# Animated_LED_Shifter_using_CD4017.net
KiCad netlist of a schematic drawn in EAGLE
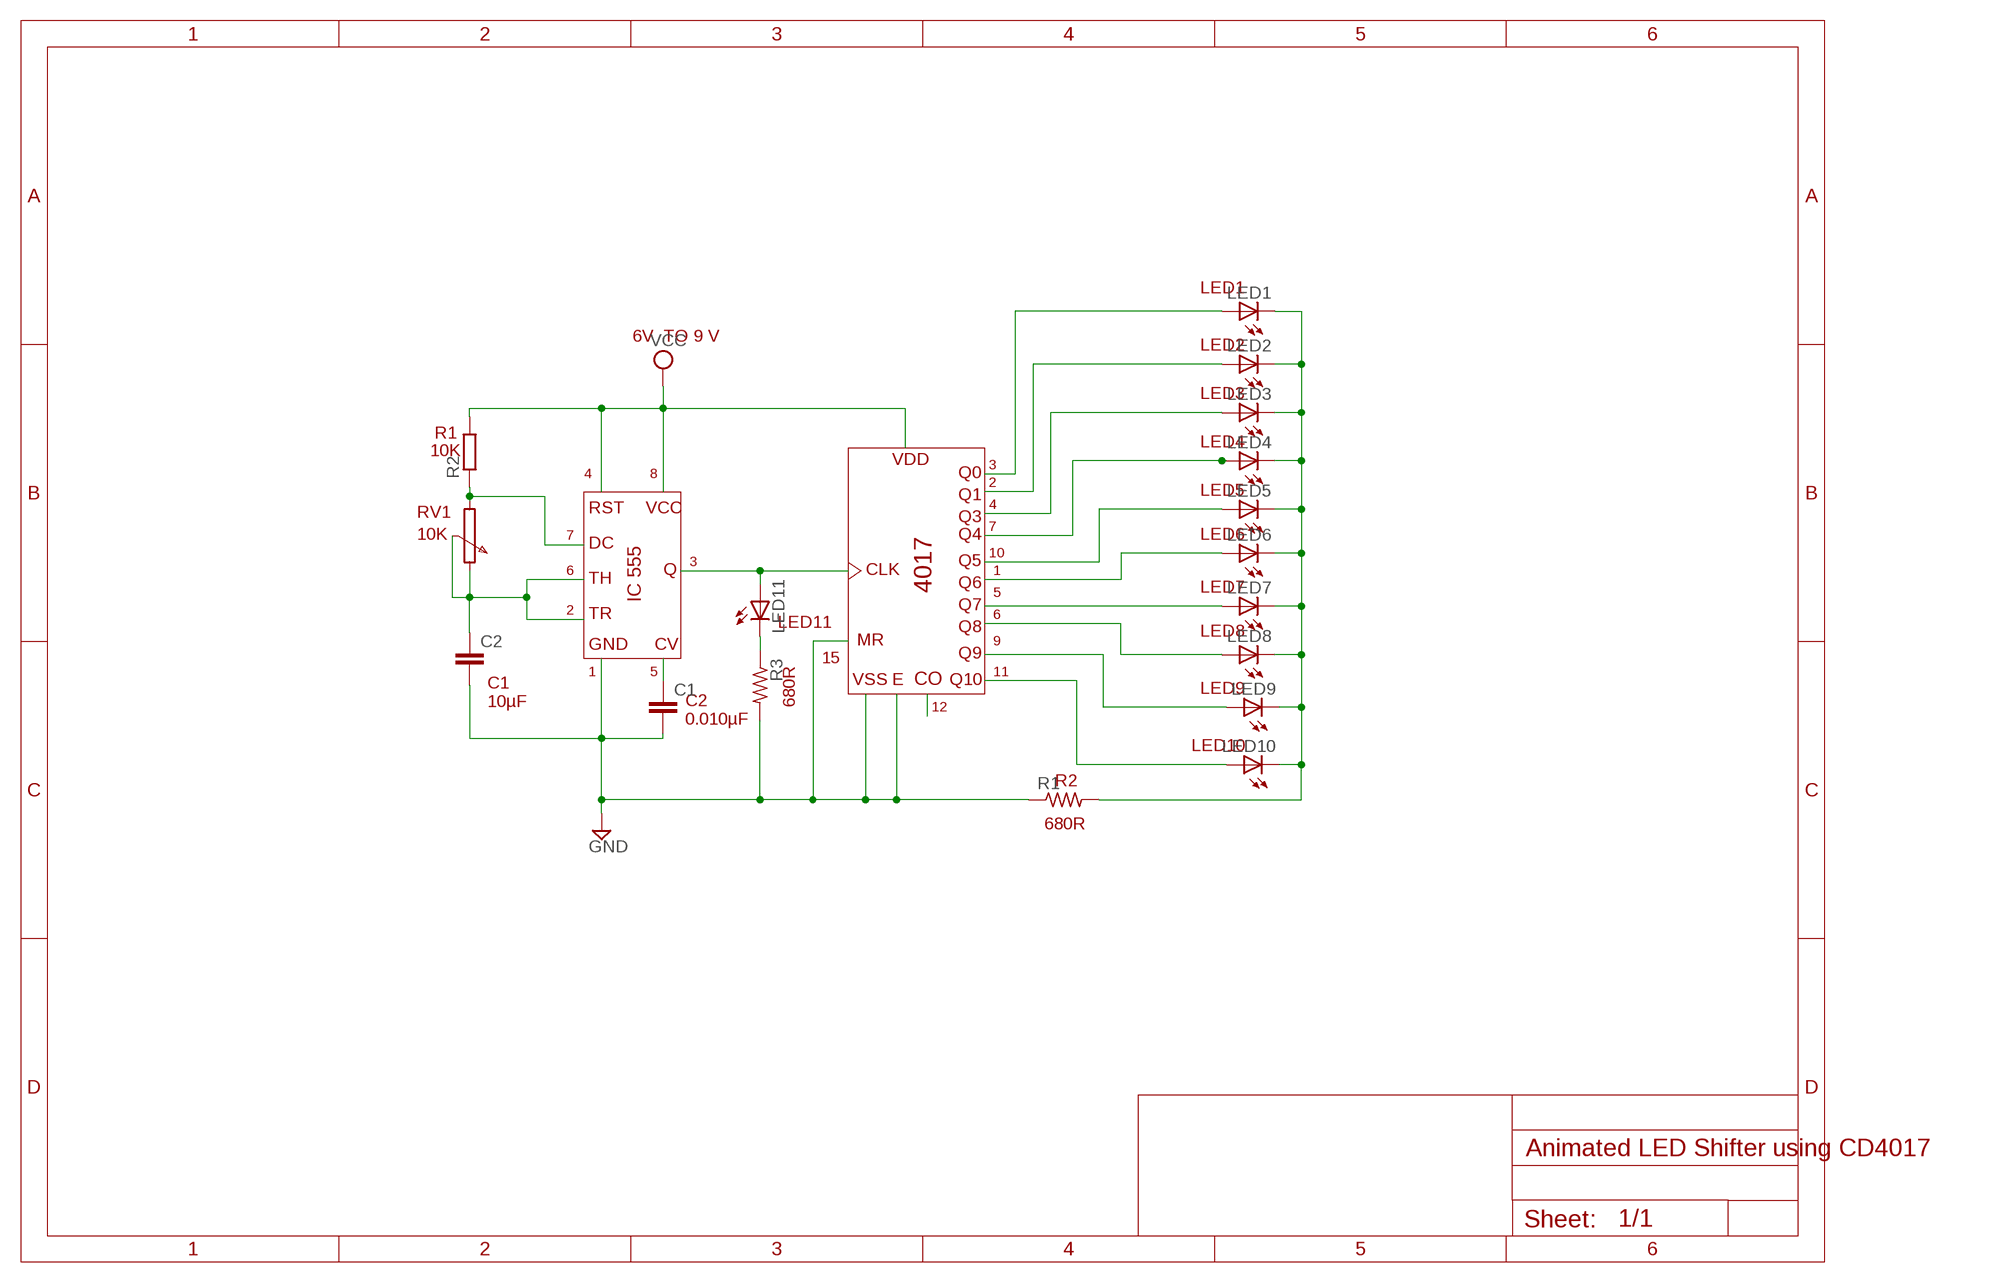
[diagram p0: schematic, sheet 1]

(export (version "E")
  (design (tool "Eeschema 10.0.6"))
  (components
    (comp (ref "C1")
      (value "C5/3.5")
      (footprint "eagle-import:C5B3.5")
      (libsource (lib "eagle-import") (part "C5/3.5"))
    )
    (comp (ref "C2")
      (value "C5/3.5")
      (footprint "eagle-import:C5B3.5")
      (libsource (lib "eagle-import") (part "C5/3.5"))
    )
    (comp (ref "LED1")
      (value "LEDMICRO-SIDELED")
      (footprint "eagle-import:MICRO-SIDELED")
      (libsource (lib "eagle-import") (part "LEDMICRO-SIDELED"))
    )
    (comp (ref "LED2")
      (value "LEDMICRO-SIDELED")
      (footprint "eagle-import:MICRO-SIDELED")
      (libsource (lib "eagle-import") (part "LEDMICRO-SIDELED"))
    )
    (comp (ref "LED3")
      (value "LEDMICRO-SIDELED")
      (footprint "eagle-import:MICRO-SIDELED")
      (libsource (lib "eagle-import") (part "LEDMICRO-SIDELED"))
    )
    (comp (ref "LED4")
      (value "LEDMICRO-SIDELED")
      (footprint "eagle-import:MICRO-SIDELED")
      (libsource (lib "eagle-import") (part "LEDMICRO-SIDELED"))
    )
    (comp (ref "LED5")
      (value "LEDMICRO-SIDELED")
      (footprint "eagle-import:MICRO-SIDELED")
      (libsource (lib "eagle-import") (part "LEDMICRO-SIDELED"))
    )
    (comp (ref "LED6")
      (value "LEDMICRO-SIDELED")
      (footprint "eagle-import:MICRO-SIDELED")
      (libsource (lib "eagle-import") (part "LEDMICRO-SIDELED"))
    )
    (comp (ref "LED7")
      (value "LEDMICRO-SIDELED")
      (footprint "eagle-import:MICRO-SIDELED")
      (libsource (lib "eagle-import") (part "LEDMICRO-SIDELED"))
    )
    (comp (ref "LED8")
      (value "LEDMICRO-SIDELED")
      (footprint "eagle-import:MICRO-SIDELED")
      (libsource (lib "eagle-import") (part "LEDMICRO-SIDELED"))
    )
    (comp (ref "LED9")
      (value "LEDMICRO-SIDELED")
      (footprint "eagle-import:MICRO-SIDELED")
      (libsource (lib "eagle-import") (part "LEDMICRO-SIDELED"))
    )
    (comp (ref "LED10")
      (value "LEDMICRO-SIDELED")
      (footprint "eagle-import:MICRO-SIDELED")
      (libsource (lib "eagle-import") (part "LEDMICRO-SIDELED"))
    )
    (comp (ref "LED11")
      (value "LEDMICRO-SIDELED")
      (footprint "eagle-import:MICRO-SIDELED")
      (libsource (lib "eagle-import") (part "LEDMICRO-SIDELED"))
    )
    (comp (ref "R1")
      (value "R-US_0207/10")
      (footprint "eagle-import:0207_10")
      (libsource (lib "eagle-import") (part "R-US_0207/10"))
    )
    (comp (ref "R2")
      (value "R-EU_0207/12")
      (footprint "eagle-import:0207_12")
      (libsource (lib "eagle-import") (part "R-EU_0207/12"))
    )
    (comp (ref "R3")
      (value "R-US_0207/10")
      (footprint "eagle-import:0207_10")
      (libsource (lib "eagle-import") (part "R-US_0207/10"))
    )
  )
  (nets
    (net (code "1") (name "GND") (class "Default")
      (node (ref "C1") (pin "2") (pinfunction "2_2") (pintype "passive"))
      (node (ref "C2") (pin "2") (pinfunction "2_2") (pintype "passive"))
      (node (ref "R1") (pin "1") (pinfunction "1_1") (pintype "passive"))
      (node (ref "R3") (pin "2") (pinfunction "2_2") (pintype "passive"))
    )
    (net (code "2") (name "Net-(LED1-PadC)") (class "Default")
      (node (ref "LED1") (pin "C") (pinfunction "C_C") (pintype "passive"))
      (node (ref "LED10") (pin "C") (pinfunction "C_C") (pintype "passive"))
      (node (ref "LED2") (pin "C") (pinfunction "C_C") (pintype "passive"))
      (node (ref "LED3") (pin "C") (pinfunction "C_C") (pintype "passive"))
      (node (ref "LED4") (pin "C") (pinfunction "C_C") (pintype "passive"))
      (node (ref "LED5") (pin "C") (pinfunction "C_C") (pintype "passive"))
      (node (ref "LED6") (pin "C") (pinfunction "C_C") (pintype "passive"))
      (node (ref "LED7") (pin "C") (pinfunction "C_C") (pintype "passive"))
      (node (ref "LED8") (pin "C") (pinfunction "C_C") (pintype "passive"))
      (node (ref "LED9") (pin "C") (pinfunction "C_C") (pintype "passive"))
      (node (ref "R1") (pin "2") (pinfunction "2_2") (pintype "passive"))
    )
    (net (code "3") (name "Net-(LED11-PadC)") (class "Default")
      (node (ref "LED11") (pin "C") (pinfunction "C_C") (pintype "passive"))
      (node (ref "R3") (pin "1") (pinfunction "1_1") (pintype "passive"))
    )
    (net (code "4") (name "VCC") (class "Default")
      (node (ref "R2") (pin "2") (pinfunction "2_2") (pintype "passive"))
    )
    (net (code "5") (name "unconnected-(C1-Pad1)") (class "Default")
      (node (ref "C1") (pin "1") (pinfunction "1_1") (pintype "passive"))
    )
    (net (code "6") (name "unconnected-(C2-Pad1)") (class "Default")
      (node (ref "C2") (pin "1") (pinfunction "1_1") (pintype "passive"))
    )
    (net (code "7") (name "unconnected-(LED1-PadA)") (class "Default")
      (node (ref "LED1") (pin "A") (pinfunction "A_A") (pintype "passive"))
    )
    (net (code "8") (name "unconnected-(LED2-PadA)") (class "Default")
      (node (ref "LED2") (pin "A") (pinfunction "A_A") (pintype "passive"))
    )
    (net (code "9") (name "unconnected-(LED3-PadA)") (class "Default")
      (node (ref "LED3") (pin "A") (pinfunction "A_A") (pintype "passive"))
    )
    (net (code "10") (name "unconnected-(LED4-PadA)") (class "Default")
      (node (ref "LED4") (pin "A") (pinfunction "A_A") (pintype "passive"))
    )
    (net (code "11") (name "unconnected-(LED5-PadA)") (class "Default")
      (node (ref "LED5") (pin "A") (pinfunction "A_A") (pintype "passive"))
    )
    (net (code "12") (name "unconnected-(LED6-PadA)") (class "Default")
      (node (ref "LED6") (pin "A") (pinfunction "A_A") (pintype "passive"))
    )
    (net (code "13") (name "unconnected-(LED7-PadA)") (class "Default")
      (node (ref "LED7") (pin "A") (pinfunction "A_A") (pintype "passive"))
    )
    (net (code "14") (name "unconnected-(LED8-PadA)") (class "Default")
      (node (ref "LED8") (pin "A") (pinfunction "A_A") (pintype "passive"))
    )
    (net (code "15") (name "unconnected-(LED9-PadA)") (class "Default")
      (node (ref "LED9") (pin "A") (pinfunction "A_A") (pintype "passive"))
    )
    (net (code "16") (name "unconnected-(LED10-PadA)") (class "Default")
      (node (ref "LED10") (pin "A") (pinfunction "A_A") (pintype "passive"))
    )
    (net (code "17") (name "unconnected-(LED11-PadA)") (class "Default")
      (node (ref "LED11") (pin "A") (pinfunction "A_A") (pintype "passive"))
    )
    (net (code "18") (name "unconnected-(R2-Pad1)") (class "Default")
      (node (ref "R2") (pin "1") (pinfunction "1_1") (pintype "passive"))
    )
  )
)
